# oven.net
KiCad netlist of a schematic drawn in EAGLE
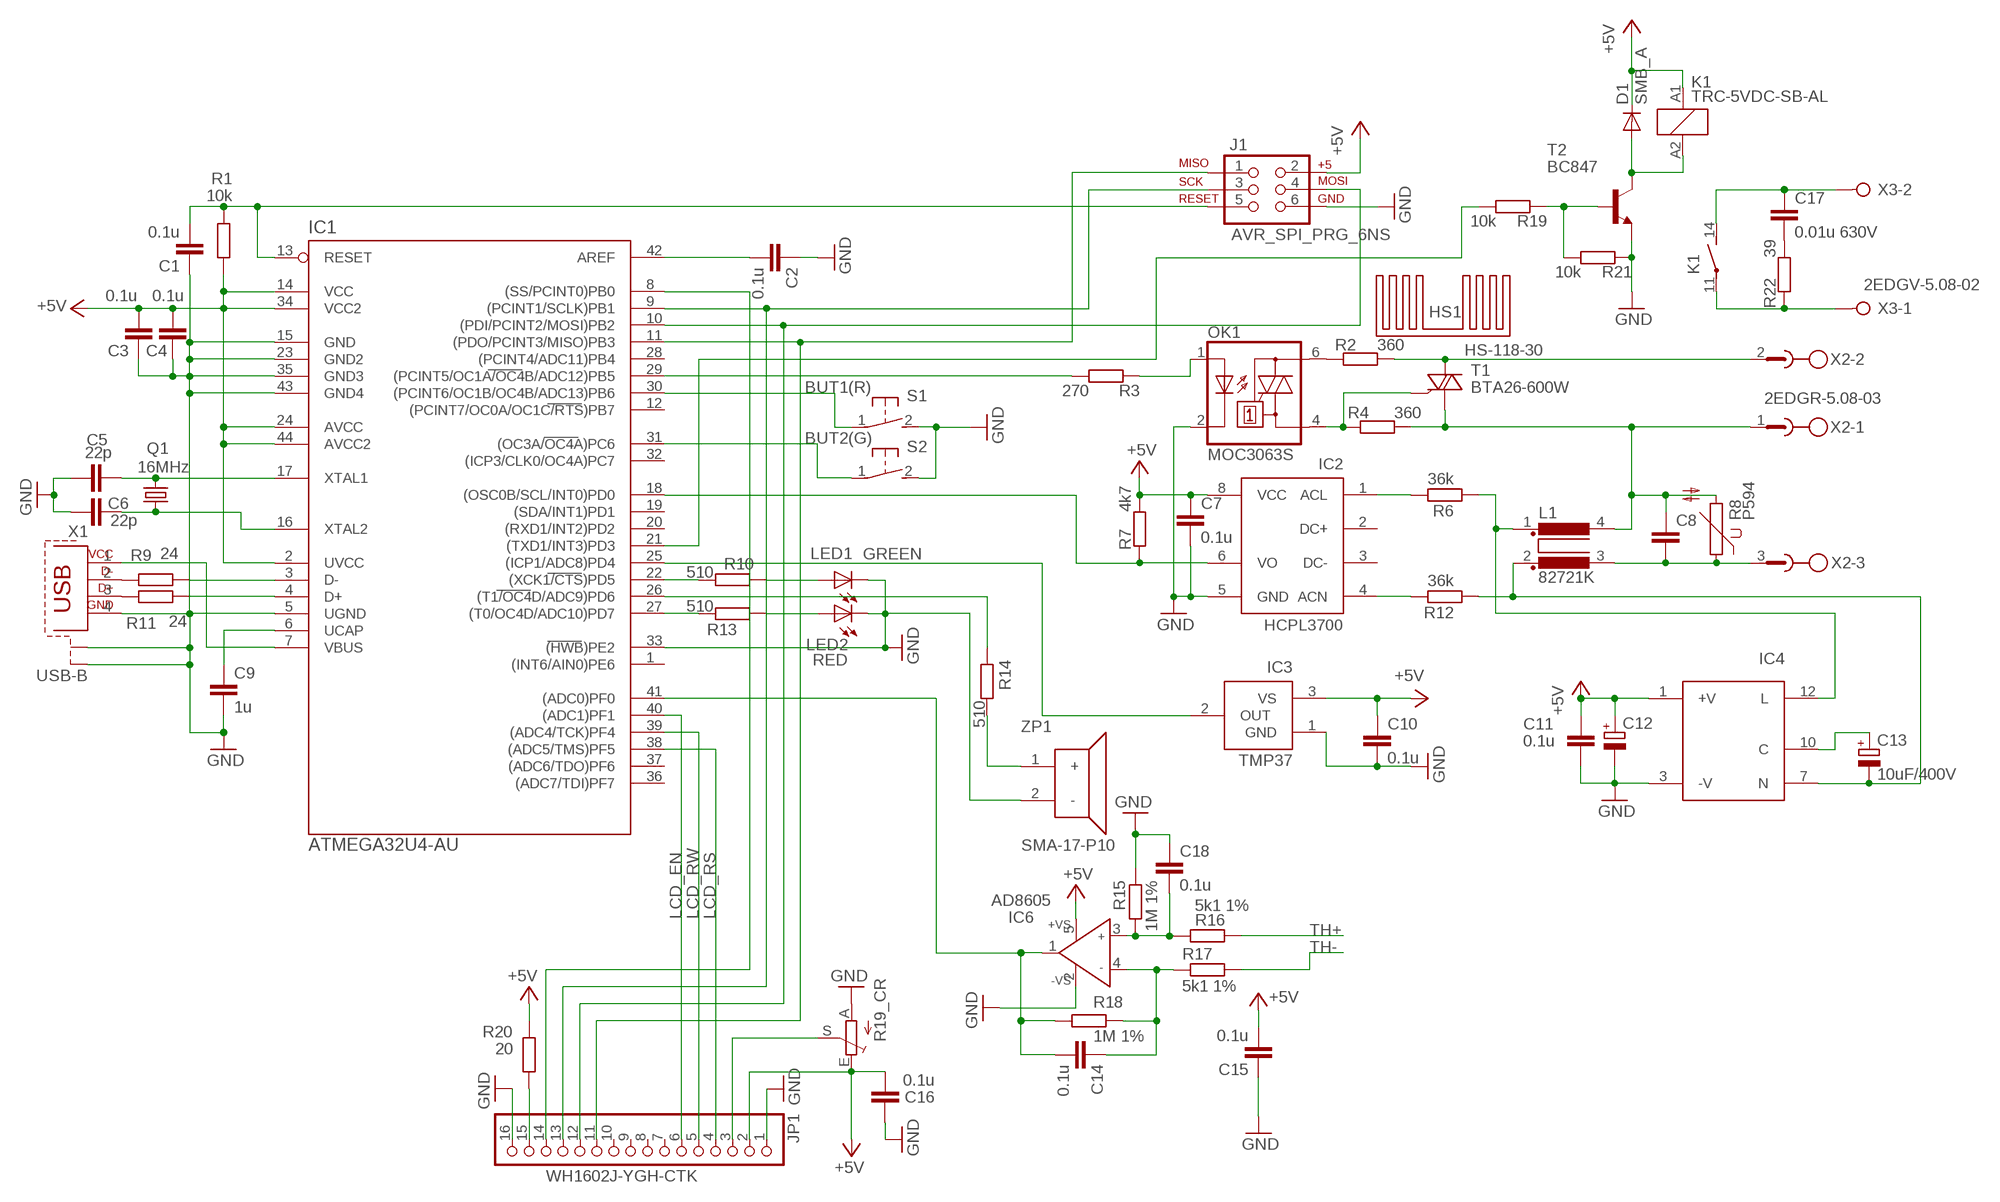
[diagram p0: schematic, sheet 1]

(export (version "E")
  (design (tool "Eeschema 10.0.6"))
  (components
    (comp (ref "C1")
      (value "0.1u")
      (footprint "eagle-import:C0805R")
      (libsource (lib "eagle-import") (part "C-EUC0805R"))
    )
    (comp (ref "C2")
      (value "0.1u")
      (footprint "eagle-import:C0805R")
      (libsource (lib "eagle-import") (part "C-EUC0805R"))
    )
    (comp (ref "C3")
      (value "0.1u")
      (footprint "eagle-import:C0805R")
      (libsource (lib "eagle-import") (part "C-EUC0805R"))
    )
    (comp (ref "C4")
      (value "0.1u")
      (footprint "eagle-import:C0805R")
      (libsource (lib "eagle-import") (part "C-EUC0805R"))
    )
    (comp (ref "C5")
      (value "22p")
      (footprint "eagle-import:C0805R")
      (libsource (lib "eagle-import") (part "C-EUC0805R"))
    )
    (comp (ref "C6")
      (value "22p")
      (footprint "eagle-import:C0805R")
      (libsource (lib "eagle-import") (part "C-EUC0805R"))
    )
    (comp (ref "C7")
      (value "0.1u")
      (footprint "eagle-import:C0805R")
      (libsource (lib "eagle-import") (part "C-EUC0805R"))
    )
    (comp (ref "C8")
      (value "C-EU102-054X133")
      (footprint "eagle-import:C102-054X133")
      (libsource (lib "eagle-import") (part "C-EU102-054X133"))
    )
    (comp (ref "C9")
      (value "1u")
      (footprint "eagle-import:C0805R")
      (libsource (lib "eagle-import") (part "C-EUC0805R"))
    )
    (comp (ref "C10")
      (value "0.1u")
      (footprint "eagle-import:C0805R")
      (libsource (lib "eagle-import") (part "C-EUC0805R"))
    )
    (comp (ref "C11")
      (value "0.1u")
      (footprint "eagle-import:C0805R")
      (libsource (lib "eagle-import") (part "C-EUC0805R"))
    )
    (comp (ref "C12")
      (value "CPOL-EUE3.5-8")
      (footprint "eagle-import:E3,5-8")
      (libsource (lib "eagle-import") (part "CPOL-EUE3.5-8"))
    )
    (comp (ref "C13")
      (value "10uF/400V")
      (footprint "eagle-import:E5-10,5")
      (libsource (lib "eagle-import") (part "CPOL-EUE5-10.5"))
    )
    (comp (ref "C14")
      (value "0.1u")
      (footprint "eagle-import:C0805R")
      (libsource (lib "eagle-import") (part "C-EUC0805R"))
    )
    (comp (ref "C15")
      (value "0.1u")
      (footprint "eagle-import:C0805R")
      (libsource (lib "eagle-import") (part "C-EUC0805R"))
    )
    (comp (ref "C16")
      (value "0.1u")
      (footprint "eagle-import:C0805R")
      (libsource (lib "eagle-import") (part "C-EUC0805R"))
    )
    (comp (ref "C17")
      (value "0.01u 630V")
      (footprint "eagle-import:C102-043X133")
      (libsource (lib "eagle-import") (part "C-EU102-043X133"))
    )
    (comp (ref "C18")
      (value "0.1u")
      (footprint "eagle-import:C0805R")
      (libsource (lib "eagle-import") (part "C-EUC0805R"))
    )
    (comp (ref "D1")
      (value "SMB_A")
      (footprint "eagle-import:DO-214AC")
      (libsource (lib "eagle-import") (part "DIODE-DO-214AC"))
    )
    (comp (ref "HS1")
      (value "HS-118-30")
      (footprint "eagle-import:HS-118")
      (libsource (lib "eagle-import") (part "HS-118"))
    )
    (comp (ref "IC1")
      (value "ATMEGA32U4-AU")
      (footprint "eagle-import:TQFP44")
      (libsource (lib "eagle-import") (part "ATMEGA32U4-AU"))
    )
    (comp (ref "IC2")
      (value "HCPL3700")
      (footprint "eagle-import:DIL08")
      (libsource (lib "eagle-import") (part "HCPL3700"))
    )
    (comp (ref "IC3")
      (value "TMP37")
      (footprint "eagle-import:TO92")
      (libsource (lib "eagle-import") (part "TMP36"))
    )
    (comp (ref "IC4")
      (value "PPM2.5-S12-05ELF")
      (footprint "eagle-import:SIP12")
      (libsource (lib "eagle-import") (part "PPM2.5-S12-05ELF"))
    )
    (comp (ref "IC6")
      (value "AD8605")
      (footprint "eagle-import:SOT23-5")
      (libsource (lib "eagle-import") (part "AD8605"))
    )
    (comp (ref "J1")
      (value "AVR_SPI_PRG_6NS")
      (footprint "eagle-import:2X3-NS")
      (libsource (lib "eagle-import") (part "AVR_SPI_PRG_6NS"))
    )
    (comp (ref "JP1")
      (value "WH1602J-YGH-CTK")
      (footprint "eagle-import:1X16")
      (libsource (lib "eagle-import") (part "PINHD-1X16"))
    )
    (comp (ref "K1")
      (value "TRC-5VDC-SB-AL")
      (footprint "eagle-import:TRC")
      (libsource (lib "eagle-import") (part "TRCA"))
    )
    (comp (ref "L1")
      (value "82721K")
      (footprint "eagle-import:82721K")
      (libsource (lib "eagle-import") (part "82721K"))
    )
    (comp (ref "LED1")
      (value "GREEN")
      (footprint "eagle-import:LED3MM")
      (libsource (lib "eagle-import") (part "LED3MM"))
    )
    (comp (ref "LED2")
      (value "RED")
      (footprint "eagle-import:LED3MM")
      (libsource (lib "eagle-import") (part "LED3MM"))
    )
    (comp (ref "OK1")
      (value "MOC3063S")
      (footprint "eagle-import:DIL6-SMD")
      (fields (field (name "MF") "FAIRCHILD SEMICONDUCTOR") (field (name "MPN") "MOC3043SM"))
      (libsource (lib "eagle-import") (part "MOC30S43"))
    )
    (comp (ref "Q1")
      (value "16MHz")
      (footprint "eagle-import:HC49_S")
      (libsource (lib "eagle-import") (part "CRYSTALHC49S"))
    )
    (comp (ref "R1")
      (value "10k")
      (footprint "eagle-import:R0805R")
      (libsource (lib "eagle-import") (part "R-EU_R0805R"))
    )
    (comp (ref "R2")
      (value "360")
      (footprint "eagle-import:R2512")
      (libsource (lib "eagle-import") (part "R-EU_R2512"))
    )
    (comp (ref "R3")
      (value "270")
      (footprint "eagle-import:R0805R")
      (libsource (lib "eagle-import") (part "R-EU_R0805R"))
    )
    (comp (ref "R4")
      (value "360")
      (footprint "eagle-import:R2512")
      (libsource (lib "eagle-import") (part "R-EU_R2512"))
    )
    (comp (ref "R6")
      (value "36k")
      (footprint "eagle-import:R1206R")
      (libsource (lib "eagle-import") (part "R-EU_R1206R"))
    )
    (comp (ref "R7")
      (value "4k7")
      (footprint "eagle-import:R0805R")
      (libsource (lib "eagle-import") (part "R-EU_R0805R"))
    )
    (comp (ref "R8")
      (value "P594")
      (footprint "eagle-import:P594")
      (libsource (lib "eagle-import") (part "P594"))
    )
    (comp (ref "R9")
      (value "24")
      (footprint "eagle-import:R0805R")
      (libsource (lib "eagle-import") (part "R-EU_R0805R"))
    )
    (comp (ref "R10")
      (value "510")
      (footprint "eagle-import:R0805R")
      (libsource (lib "eagle-import") (part "R-EU_R0805R"))
    )
    (comp (ref "R11")
      (value "24")
      (footprint "eagle-import:R0805R")
      (libsource (lib "eagle-import") (part "R-EU_R0805R"))
    )
    (comp (ref "R12")
      (value "36k")
      (footprint "eagle-import:R1206R")
      (libsource (lib "eagle-import") (part "R-EU_R1206R"))
    )
    (comp (ref "R13")
      (value "510")
      (footprint "eagle-import:R0805R")
      (libsource (lib "eagle-import") (part "R-EU_R0805R"))
    )
    (comp (ref "R14")
      (value "510")
      (footprint "eagle-import:R0805R")
      (libsource (lib "eagle-import") (part "R-EU_R0805R"))
    )
    (comp (ref "R15")
      (value "1M 1%")
      (footprint "eagle-import:R0805R")
      (libsource (lib "eagle-import") (part "R-EU_R0805R"))
    )
    (comp (ref "R16")
      (value "5k1 1%")
      (footprint "eagle-import:R0805R")
      (libsource (lib "eagle-import") (part "R-EU_R0805R"))
    )
    (comp (ref "R17")
      (value "5k1 1%")
      (footprint "eagle-import:R0805R")
      (libsource (lib "eagle-import") (part "R-EU_R0805R"))
    )
    (comp (ref "R18")
      (value "1M 1%")
      (footprint "eagle-import:R0805R")
      (libsource (lib "eagle-import") (part "R-EU_R0805R"))
    )
    (comp (ref "R19")
      (value "10k")
      (footprint "eagle-import:R0805R")
      (libsource (lib "eagle-import") (part "R-EU_R0805R"))
    )
    (comp (ref "R19_CR")
      (value "TRIM_EU-CA6V")
      (footprint "eagle-import:CA6V")
      (libsource (lib "eagle-import") (part "TRIM_EU-CA6V"))
    )
    (comp (ref "R20")
      (value "20")
      (footprint "eagle-import:R0805R")
      (libsource (lib "eagle-import") (part "R-EU_R0805R"))
    )
    (comp (ref "R21")
      (value "10k")
      (footprint "eagle-import:R0805R")
      (libsource (lib "eagle-import") (part "R-EU_R0805R"))
    )
    (comp (ref "R22")
      (value "39")
      (footprint "eagle-import:0207_5V")
      (libsource (lib "eagle-import") (part "R-EU_0207/5V"))
    )
    (comp (ref "S1")
      (value "31-XX")
      (footprint "eagle-import:B3F-31XX")
      (fields (field (name "MPN") "B3F-3100"))
      (libsource (lib "eagle-import") (part "31-XX"))
    )
    (comp (ref "S2")
      (value "31-XX")
      (footprint "eagle-import:B3F-31XX")
      (fields (field (name "MPN") "B3F-3100"))
      (libsource (lib "eagle-import") (part "31-XX"))
    )
    (comp (ref "T1")
      (value "BTA26-600W")
      (footprint "eagle-import:TOP3S-1")
      (libsource (lib "eagle-import") (part "BTA26-V"))
    )
    (comp (ref "T2")
      (value "BC847")
      (footprint "eagle-import:SOT23")
      (libsource (lib "eagle-import") (part "BC847"))
    )
    (comp (ref "X1")
      (value "USB-B")
      (footprint "eagle-import:PN61729-S")
      (libsource (lib "eagle-import") (part "USB-B"))
    )
    (comp (ref "X2")
      (value "2EDGR-5.08-03")
      (footprint "eagle-import:W232-3")
      (libsource (lib "eagle-import") (part "W232-3"))
    )
    (comp (ref "X3")
      (value "2EDGV-5.08-02")
      (footprint "eagle-import:W237-132")
      (libsource (lib "eagle-import") (part "W237-02P"))
    )
    (comp (ref "ZP1")
      (value "SMA-17-P10")
      (footprint "eagle-import:SMA-17")
      (libsource (lib "eagle-import") (part "SMA-17-P10"))
    )
  )
  (nets
    (net (code "1") (name "+5V") (class "Default")
      (node (ref "C10") (pin "1") (pinfunction "1_1") (pintype "passive"))
      (node (ref "C11") (pin "1") (pinfunction "1_1") (pintype "passive"))
      (node (ref "C12") (pin "+") (pinfunction "+_+") (pintype "passive"))
      (node (ref "C15") (pin "2") (pinfunction "2_2") (pintype "passive"))
      (node (ref "C16") (pin "2") (pinfunction "2_2") (pintype "passive"))
      (node (ref "C3") (pin "2") (pinfunction "2_2") (pintype "passive"))
      (node (ref "C4") (pin "2") (pinfunction "2_2") (pintype "passive"))
      (node (ref "C7") (pin "1") (pinfunction "1_1") (pintype "passive"))
      (node (ref "D1") (pin "C") (pinfunction "C_C") (pintype "passive"))
      (node (ref "IC1") (pin "14") (pinfunction "VCC_14") (pintype "bidirectional"))
      (node (ref "IC1") (pin "2") (pinfunction "UVCC_2") (pintype "bidirectional"))
      (node (ref "IC1") (pin "24") (pinfunction "AVCC_24") (pintype "bidirectional"))
      (node (ref "IC1") (pin "34") (pinfunction "VCC2_34") (pintype "bidirectional"))
      (node (ref "IC1") (pin "44") (pinfunction "AVCC2_44") (pintype "bidirectional"))
      (node (ref "IC2") (pin "8") (pinfunction "VCC_8") (pintype "power_in"))
      (node (ref "IC3") (pin "3") (pinfunction "VS_3") (pintype "power_in"))
      (node (ref "IC4") (pin "1") (pinfunction "+V_1") (pintype "bidirectional"))
      (node (ref "IC6") (pin "5") (pinfunction "+VS_5") (pintype "input"))
      (node (ref "J1") (pin "2") (pinfunction "2_2") (pintype "passive"))
      (node (ref "JP1") (pin "2") (pinfunction "2_2") (pintype "passive"))
      (node (ref "K1") (pin "A1") (pinfunction "1_A1") (pintype "passive"))
      (node (ref "R1") (pin "1") (pinfunction "1_1") (pintype "passive"))
      (node (ref "R19_CR") (pin "E") (pinfunction "E_E") (pintype "passive"))
      (node (ref "R20") (pin "1") (pinfunction "1_1") (pintype "passive"))
      (node (ref "R7") (pin "2") (pinfunction "2_2") (pintype "passive"))
    )
    (net (code "2") (name "/BUT1(R)") (class "Default")
      (node (ref "IC1") (pin "30") (pinfunction "(PCINT6/OC1B/OC4B/ADC13)PB6_30") (pintype "bidirectional"))
      (node (ref "S1") (pin "1") (pinfunction "P_1") (pintype "passive"))
    )
    (net (code "3") (name "/BUT2(G)") (class "Default")
      (node (ref "IC1") (pin "31") (pinfunction "(OC3A/OC4A)PC6_31") (pintype "bidirectional"))
      (node (ref "S2") (pin "1") (pinfunction "P_1") (pintype "passive"))
    )
    (net (code "4") (name "/LCD_EN") (class "Default")
      (node (ref "IC1") (pin "40") (pinfunction "(ADC1)PF1_40") (pintype "bidirectional"))
      (node (ref "JP1") (pin "6") (pinfunction "6_6") (pintype "passive"))
    )
    (net (code "5") (name "/LCD_RS") (class "Default")
      (node (ref "IC1") (pin "38") (pinfunction "(ADC5/TMS)PF5_38") (pintype "bidirectional"))
      (node (ref "JP1") (pin "4") (pinfunction "4_4") (pintype "passive"))
    )
    (net (code "6") (name "/LCD_RW") (class "Default")
      (node (ref "IC1") (pin "39") (pinfunction "(ADC4/TCK)PF4_39") (pintype "bidirectional"))
      (node (ref "JP1") (pin "5") (pinfunction "5_5") (pintype "passive"))
    )
    (net (code "7") (name "/TH+") (class "Default")
      (node (ref "R16") (pin "2") (pinfunction "2_2") (pintype "passive"))
    )
    (net (code "8") (name "/TH-") (class "Default")
      (node (ref "R17") (pin "2") (pinfunction "2_2") (pintype "passive"))
    )
    (net (code "9") (name "GND") (class "Default")
      (node (ref "C1") (pin "1") (pinfunction "1_1") (pintype "passive"))
      (node (ref "C10") (pin "2") (pinfunction "2_2") (pintype "passive"))
      (node (ref "C11") (pin "2") (pinfunction "2_2") (pintype "passive"))
      (node (ref "C12") (pin "-") (pinfunction "-_-") (pintype "passive"))
      (node (ref "C15") (pin "1") (pinfunction "1_1") (pintype "passive"))
      (node (ref "C16") (pin "1") (pinfunction "1_1") (pintype "passive"))
      (node (ref "C18") (pin "1") (pinfunction "1_1") (pintype "passive"))
      (node (ref "C2") (pin "1") (pinfunction "1_1") (pintype "passive"))
      (node (ref "C3") (pin "1") (pinfunction "1_1") (pintype "passive"))
      (node (ref "C4") (pin "1") (pinfunction "1_1") (pintype "passive"))
      (node (ref "C5") (pin "1") (pinfunction "1_1") (pintype "passive"))
      (node (ref "C6") (pin "1") (pinfunction "1_1") (pintype "passive"))
      (node (ref "C7") (pin "2") (pinfunction "2_2") (pintype "passive"))
      (node (ref "C9") (pin "2") (pinfunction "2_2") (pintype "passive"))
      (node (ref "IC1") (pin "15") (pinfunction "GND_15") (pintype "bidirectional"))
      (node (ref "IC1") (pin "23") (pinfunction "GND2_23") (pintype "bidirectional"))
      (node (ref "IC1") (pin "33") (pinfunction "(HWB)PE2_33") (pintype "bidirectional"))
      (node (ref "IC1") (pin "35") (pinfunction "GND3_35") (pintype "bidirectional"))
      (node (ref "IC1") (pin "43") (pinfunction "GND4_43") (pintype "bidirectional"))
      (node (ref "IC1") (pin "5") (pinfunction "UGND_5") (pintype "bidirectional"))
      (node (ref "IC2") (pin "5") (pinfunction "GND_5") (pintype "power_in"))
      (node (ref "IC3") (pin "1") (pinfunction "GND_1") (pintype "power_in"))
      (node (ref "IC4") (pin "3") (pinfunction "-V_3") (pintype "bidirectional"))
      (node (ref "IC6") (pin "2") (pinfunction "-VS_2") (pintype "input"))
      (node (ref "J1") (pin "6") (pinfunction "6_6") (pintype "passive"))
      (node (ref "JP1") (pin "1") (pinfunction "1_1") (pintype "passive"))
      (node (ref "JP1") (pin "16") (pinfunction "16_16") (pintype "passive"))
      (node (ref "LED1") (pin "K") (pinfunction "C_K") (pintype "passive"))
      (node (ref "LED2") (pin "K") (pinfunction "C_K") (pintype "passive"))
      (node (ref "OK1") (pin "2") (pinfunction "C_2") (pintype "passive"))
      (node (ref "R15") (pin "2") (pinfunction "2_2") (pintype "passive"))
      (node (ref "R19_CR") (pin "A") (pinfunction "A_A") (pintype "passive"))
      (node (ref "R21") (pin "1") (pinfunction "1_1") (pintype "passive"))
      (node (ref "S1") (pin "2") (pinfunction "S_2") (pintype "passive"))
      (node (ref "S2") (pin "2") (pinfunction "S_2") (pintype "passive"))
      (node (ref "T2") (pin "2") (pinfunction "E_2") (pintype "passive"))
      (node (ref "X1") (pin "4") (pinfunction "4_4") (pintype "passive"))
      (node (ref "X1") (pin "S1") (pinfunction "S1_S1") (pintype "passive"))
      (node (ref "X1") (pin "S2") (pinfunction "S2_S2") (pintype "passive"))
      (node (ref "ZP1") (pin "2") (pinfunction "-_2") (pintype "bidirectional"))
    )
    (net (code "10") (name "Net-(C17-Pad2)") (class "Default")
      (node (ref "C17") (pin "2") (pinfunction "2_2") (pintype "passive"))
      (node (ref "R22") (pin "2") (pinfunction "2_2") (pintype "passive"))
    )
    (net (code "11") (name "Net-(IC1-(ADC0)PF0)") (class "Default")
      (node (ref "C14") (pin "2") (pinfunction "2_2") (pintype "passive"))
      (node (ref "IC1") (pin "41") (pinfunction "(ADC0)PF0_41") (pintype "bidirectional"))
      (node (ref "IC6") (pin "1") (pinfunction "OUT_1") (pintype "output"))
      (node (ref "R18") (pin "1") (pinfunction "1_1") (pintype "passive"))
    )
    (net (code "12") (name "Net-(IC1-(ICP1{slash}ADC8)PD4)") (class "Default")
      (node (ref "IC1") (pin "25") (pinfunction "(ICP1/ADC8)PD4_25") (pintype "bidirectional"))
      (node (ref "IC3") (pin "2") (pinfunction "OUT_2") (pintype "output"))
    )
    (net (code "13") (name "Net-(IC1-(OSC0B{slash}SCL{slash}INT0)PD0)") (class "Default")
      (node (ref "IC1") (pin "18") (pinfunction "(OSC0B/SCL/INT0)PD0_18") (pintype "bidirectional"))
      (node (ref "IC2") (pin "6") (pinfunction "VO_6") (pintype "output"))
      (node (ref "R7") (pin "1") (pinfunction "1_1") (pintype "passive"))
    )
    (net (code "14") (name "Net-(IC1-(PCINT1{slash}SCLK)PB1)") (class "Default")
      (node (ref "IC1") (pin "9") (pinfunction "(PCINT1/SCLK)PB1_9") (pintype "bidirectional"))
      (node (ref "J1") (pin "3") (pinfunction "3_3") (pintype "passive"))
      (node (ref "JP1") (pin "13") (pinfunction "13_13") (pintype "passive"))
    )
    (net (code "15") (name "Net-(IC1-(PCINT5{slash}OC1A{slash}OC4B{slash}ADC12)PB5)") (class "Default")
      (node (ref "IC1") (pin "29") (pinfunction "(PCINT5/OC1A/OC4B/ADC12)PB5_29") (pintype "bidirectional"))
      (node (ref "R3") (pin "2") (pinfunction "2_2") (pintype "passive"))
    )
    (net (code "16") (name "Net-(IC1-(PDI{slash}PCINT2{slash}MOSI)PB2)") (class "Default")
      (node (ref "IC1") (pin "10") (pinfunction "(PDI/PCINT2/MOSI)PB2_10") (pintype "bidirectional"))
      (node (ref "J1") (pin "4") (pinfunction "4_4") (pintype "passive"))
      (node (ref "JP1") (pin "12") (pinfunction "12_12") (pintype "passive"))
    )
    (net (code "17") (name "Net-(IC1-(PDO{slash}PCINT3{slash}MISO)PB3)") (class "Default")
      (node (ref "IC1") (pin "11") (pinfunction "(PDO/PCINT3/MISO)PB3_11") (pintype "bidirectional"))
      (node (ref "J1") (pin "1") (pinfunction "1_1") (pintype "passive"))
      (node (ref "JP1") (pin "11") (pinfunction "11_11") (pintype "passive"))
    )
    (net (code "18") (name "Net-(IC1-(SS{slash}PCINT0)PB0)") (class "Default")
      (node (ref "IC1") (pin "8") (pinfunction "(SS/PCINT0)PB0_8") (pintype "bidirectional"))
      (node (ref "JP1") (pin "14") (pinfunction "14_14") (pintype "passive"))
    )
    (net (code "19") (name "Net-(IC1-(T0{slash}OC4D{slash}ADC10)PD7)") (class "Default")
      (node (ref "IC1") (pin "27") (pinfunction "(T0/OC4D/ADC10)PD7_27") (pintype "bidirectional"))
      (node (ref "R13") (pin "2") (pinfunction "2_2") (pintype "passive"))
    )
    (net (code "20") (name "Net-(IC1-(T1{slash}OC4D{slash}ADC9)PD6)") (class "Default")
      (node (ref "IC1") (pin "26") (pinfunction "(T1/OC4D/ADC9)PD6_26") (pintype "bidirectional"))
      (node (ref "R14") (pin "1") (pinfunction "1_1") (pintype "passive"))
    )
    (net (code "21") (name "Net-(IC1-(TXD1{slash}INT3)PD3)") (class "Default")
      (node (ref "IC1") (pin "21") (pinfunction "(TXD1/INT3)PD3_21") (pintype "bidirectional"))
      (node (ref "R19") (pin "2") (pinfunction "2_2") (pintype "passive"))
    )
    (net (code "22") (name "Net-(IC1-(XCK1{slash}CTS)PD5)") (class "Default")
      (node (ref "IC1") (pin "22") (pinfunction "(XCK1/CTS)PD5_22") (pintype "bidirectional"))
      (node (ref "R10") (pin "2") (pinfunction "2_2") (pintype "passive"))
    )
    (net (code "23") (name "Net-(IC1-AREF)") (class "Default")
      (node (ref "C2") (pin "2") (pinfunction "2_2") (pintype "passive"))
      (node (ref "IC1") (pin "42") (pinfunction "AREF_42") (pintype "bidirectional"))
    )
    (net (code "24") (name "Net-(IC1-D+)") (class "Default")
      (node (ref "IC1") (pin "4") (pinfunction "D+_4") (pintype "bidirectional"))
      (node (ref "R11") (pin "2") (pinfunction "2_2") (pintype "passive"))
    )
    (net (code "25") (name "Net-(IC1-D-)") (class "Default")
      (node (ref "IC1") (pin "3") (pinfunction "D-_3") (pintype "bidirectional"))
      (node (ref "R9") (pin "2") (pinfunction "2_2") (pintype "passive"))
    )
    (net (code "26") (name "Net-(IC1-RESET)") (class "Default")
      (node (ref "C1") (pin "2") (pinfunction "2_2") (pintype "passive"))
      (node (ref "IC1") (pin "13") (pinfunction "RESET_13") (pintype "bidirectional"))
      (node (ref "J1") (pin "5") (pinfunction "5_5") (pintype "passive"))
      (node (ref "R1") (pin "2") (pinfunction "2_2") (pintype "passive"))
    )
    (net (code "27") (name "Net-(IC1-UCAP)") (class "Default")
      (node (ref "C9") (pin "1") (pinfunction "1_1") (pintype "passive"))
      (node (ref "IC1") (pin "6") (pinfunction "UCAP_6") (pintype "bidirectional"))
    )
    (net (code "28") (name "Net-(IC1-VBUS)") (class "Default")
      (node (ref "IC1") (pin "7") (pinfunction "VBUS_7") (pintype "bidirectional"))
      (node (ref "X1") (pin "1") (pinfunction "1_1") (pintype "passive"))
    )
    (net (code "29") (name "Net-(IC1-XTAL1)") (class "Default")
      (node (ref "C5") (pin "2") (pinfunction "2_2") (pintype "passive"))
      (node (ref "IC1") (pin "17") (pinfunction "XTAL1_17") (pintype "bidirectional"))
      (node (ref "Q1") (pin "2") (pinfunction "2_2") (pintype "passive"))
    )
    (net (code "30") (name "Net-(IC1-XTAL2)") (class "Default")
      (node (ref "C6") (pin "2") (pinfunction "2_2") (pintype "passive"))
      (node (ref "IC1") (pin "16") (pinfunction "XTAL2_16") (pintype "bidirectional"))
      (node (ref "Q1") (pin "1") (pinfunction "1_1") (pintype "passive"))
    )
    (net (code "31") (name "Net-(IC2-ACL)") (class "Default")
      (node (ref "IC2") (pin "1") (pinfunction "ACL_1") (pintype "input"))
      (node (ref "R6") (pin "2") (pinfunction "2_2") (pintype "passive"))
    )
    (net (code "32") (name "Net-(IC2-ACN)") (class "Default")
      (node (ref "IC2") (pin "4") (pinfunction "ACN_4") (pintype "input"))
      (node (ref "R12") (pin "2") (pinfunction "2_2") (pintype "passive"))
    )
    (net (code "33") (name "Net-(IC4-C)") (class "Default")
      (node (ref "C13") (pin "+") (pinfunction "+_+") (pintype "passive"))
      (node (ref "IC4") (pin "10") (pinfunction "C_10") (pintype "bidirectional"))
    )
    (net (code "34") (name "Net-(IC4-L)") (class "Default")
      (node (ref "IC4") (pin "12") (pinfunction "L_12") (pintype "bidirectional"))
      (node (ref "L1") (pin "1") (pinfunction "1_1") (pintype "passive"))
      (node (ref "R6") (pin "1") (pinfunction "1_1") (pintype "passive"))
    )
    (net (code "35") (name "Net-(IC4-N)") (class "Default")
      (node (ref "C13") (pin "-") (pinfunction "-_-") (pintype "passive"))
      (node (ref "IC4") (pin "7") (pinfunction "N_7") (pintype "bidirectional"))
      (node (ref "L1") (pin "2") (pinfunction "3_2") (pintype "passive"))
      (node (ref "R12") (pin "1") (pinfunction "1_1") (pintype "passive"))
    )
    (net (code "36") (name "Net-(IC6-IN+)") (class "Default")
      (node (ref "C18") (pin "2") (pinfunction "2_2") (pintype "passive"))
      (node (ref "IC6") (pin "3") (pinfunction "IN+_3") (pintype "input"))
      (node (ref "R15") (pin "1") (pinfunction "1_1") (pintype "passive"))
      (node (ref "R16") (pin "1") (pinfunction "1_1") (pintype "passive"))
    )
    (net (code "37") (name "Net-(IC6-IN-)") (class "Default")
      (node (ref "C14") (pin "1") (pinfunction "1_1") (pintype "passive"))
      (node (ref "IC6") (pin "4") (pinfunction "IN-_4") (pintype "input"))
      (node (ref "R17") (pin "1") (pinfunction "1_1") (pintype "passive"))
      (node (ref "R18") (pin "2") (pinfunction "2_2") (pintype "passive"))
    )
    (net (code "38") (name "Net-(JP1-Pad3)") (class "Default")
      (node (ref "JP1") (pin "3") (pinfunction "3_3") (pintype "passive"))
      (node (ref "R19_CR") (pin "S") (pinfunction "S_S") (pintype "passive"))
    )
    (net (code "39") (name "Net-(JP1-Pad15)") (class "Default")
      (node (ref "JP1") (pin "15") (pinfunction "15_15") (pintype "passive"))
      (node (ref "R20") (pin "2") (pinfunction "2_2") (pintype "passive"))
    )
    (net (code "40") (name "Net-(K1A-2)") (class "Default")
      (node (ref "D1") (pin "A") (pinfunction "A_A") (pintype "passive"))
      (node (ref "K1") (pin "A2") (pinfunction "2_A2") (pintype "passive"))
      (node (ref "T2") (pin "3") (pinfunction "C_3") (pintype "passive"))
    )
    (net (code "41") (name "Net-(K1B-P)") (class "Default")
      (node (ref "K1") (pin "11") (pinfunction "P_11") (pintype "passive"))
      (node (ref "R22") (pin "1") (pinfunction "1_1") (pintype "passive"))
      (node (ref "X3") (pin "1") (pinfunction "KL_1") (pintype "passive"))
    )
    (net (code "42") (name "Net-(K1B-S)") (class "Default")
      (node (ref "C17") (pin "1") (pinfunction "1_1") (pintype "passive"))
      (node (ref "K1") (pin "14") (pinfunction "S_14") (pintype "passive"))
      (node (ref "X3") (pin "2") (pinfunction "KL_2") (pintype "passive"))
    )
    (net (code "43") (name "Net-(L1-2)") (class "Default")
      (node (ref "C8") (pin "1") (pinfunction "1_1") (pintype "passive"))
      (node (ref "L1") (pin "4") (pinfunction "2_4") (pintype "passive"))
      (node (ref "R4") (pin "2") (pinfunction "2_2") (pintype "passive"))
      (node (ref "R8") (pin "2") (pinfunction "2_2") (pintype "passive"))
      (node (ref "T1") (pin "A1") (pinfunction "A1_A1") (pintype "passive"))
      (node (ref "X2") (pin "1") (pinfunction "SK_1") (pintype "passive"))
    )
    (net (code "44") (name "Net-(L1-4)") (class "Default")
      (node (ref "C8") (pin "2") (pinfunction "2_2") (pintype "passive"))
      (node (ref "L1") (pin "3") (pinfunction "4_3") (pintype "passive"))
      (node (ref "R8") (pin "1") (pinfunction "1_1") (pintype "passive"))
      (node (ref "X2") (pin "3") (pinfunction "SK_3") (pintype "passive"))
    )
    (net (code "45") (name "Net-(LED1-PadA)") (class "Default")
      (node (ref "LED1") (pin "A") (pinfunction "A_A") (pintype "passive"))
      (node (ref "R10") (pin "1") (pinfunction "1_1") (pintype "passive"))
    )
    (net (code "46") (name "Net-(LED2-PadA)") (class "Default")
      (node (ref "LED2") (pin "A") (pinfunction "A_A") (pintype "passive"))
      (node (ref "R13") (pin "1") (pinfunction "1_1") (pintype "passive"))
    )
    (net (code "47") (name "Net-(OK1-A)") (class "Default")
      (node (ref "OK1") (pin "1") (pinfunction "A_1") (pintype "passive"))
      (node (ref "R3") (pin "1") (pinfunction "1_1") (pintype "passive"))
    )
    (net (code "48") (name "Net-(OK1-A1)") (class "Default")
      (node (ref "OK1") (pin "4") (pinfunction "A1_4") (pintype "passive"))
      (node (ref "R4") (pin "1") (pinfunction "1_1") (pintype "passive"))
      (node (ref "T1") (pin "G") (pinfunction "G_G") (pintype "passive"))
    )
    (net (code "49") (name "Net-(OK1-A2)") (class "Default")
      (node (ref "OK1") (pin "6") (pinfunction "A2_6") (pintype "passive"))
      (node (ref "R2") (pin "1") (pinfunction "1_1") (pintype "passive"))
    )
    (net (code "50") (name "Net-(R9-Pad1)") (class "Default")
      (node (ref "R9") (pin "1") (pinfunction "1_1") (pintype "passive"))
      (node (ref "X1") (pin "2") (pinfunction "2_2") (pintype "passive"))
    )
    (net (code "51") (name "Net-(R11-Pad1)") (class "Default")
      (node (ref "R11") (pin "1") (pinfunction "1_1") (pintype "passive"))
      (node (ref "X1") (pin "3") (pinfunction "3_3") (pintype "passive"))
    )
    (net (code "52") (name "Net-(T2-B)") (class "Default")
      (node (ref "R19") (pin "1") (pinfunction "1_1") (pintype "passive"))
      (node (ref "R21") (pin "2") (pinfunction "2_2") (pintype "passive"))
      (node (ref "T2") (pin "1") (pinfunction "B_1") (pintype "passive"))
    )
    (net (code "53") (name "Net-(X2B-SK)") (class "Default")
      (node (ref "R2") (pin "2") (pinfunction "2_2") (pintype "passive"))
      (node (ref "T1") (pin "A2") (pinfunction "A2_A2") (pintype "passive"))
      (node (ref "X2") (pin "2") (pinfunction "SK_2") (pintype "passive"))
    )
    (net (code "54") (name "Net-(ZP1-+)") (class "Default")
      (node (ref "R14") (pin "2") (pinfunction "2_2") (pintype "passive"))
      (node (ref "ZP1") (pin "1") (pinfunction "+_1") (pintype "bidirectional"))
    )
    (net (code "55") (name "unconnected-(IC1-(ADC6{slash}TDO)PF6-Pad37)") (class "Default")
      (node (ref "IC1") (pin "37") (pinfunction "(ADC6/TDO)PF6_37") (pintype "bidirectional"))
    )
    (net (code "56") (name "unconnected-(IC1-(ADC7{slash}TDI)PF7-Pad36)") (class "Default")
      (node (ref "IC1") (pin "36") (pinfunction "(ADC7/TDI)PF7_36") (pintype "bidirectional"))
    )
    (net (code "57") (name "unconnected-(IC1-(ICP3{slash}CLK0{slash}OC4A)PC7-Pad32)") (class "Default")
      (node (ref "IC1") (pin "32") (pinfunction "(ICP3/CLK0/OC4A)PC7_32") (pintype "bidirectional"))
    )
    (net (code "58") (name "unconnected-(IC1-(INT6{slash}AIN0)PE6-Pad1)") (class "Default")
      (node (ref "IC1") (pin "1") (pinfunction "(INT6/AIN0)PE6_1") (pintype "bidirectional"))
    )
    (net (code "59") (name "unconnected-(IC1-(PCINT4{slash}ADC11)PB4-Pad28)") (class "Default")
      (node (ref "IC1") (pin "28") (pinfunction "(PCINT4/ADC11)PB4_28") (pintype "bidirectional"))
    )
    (net (code "60") (name "unconnected-(IC1-(PCINT7{slash}OC0A{slash}OC1C{slash}RTS)PB7-Pad12)") (class "Default")
      (node (ref "IC1") (pin "12") (pinfunction "(PCINT7/OC0A/OC1C/RTS)PB7_12") (pintype "bidirectional"))
    )
    (net (code "61") (name "unconnected-(IC1-(RXD1{slash}INT2)PD2-Pad20)") (class "Default")
      (node (ref "IC1") (pin "20") (pinfunction "(RXD1/INT2)PD2_20") (pintype "bidirectional"))
    )
    (net (code "62") (name "unconnected-(IC1-(SDA{slash}INT1)PD1-Pad19)") (class "Default")
      (node (ref "IC1") (pin "19") (pinfunction "(SDA/INT1)PD1_19") (pintype "bidirectional"))
    )
    (net (code "63") (name "unconnected-(IC2-DC+-Pad2)") (class "Default")
      (node (ref "IC2") (pin "2") (pinfunction "DC+_2") (pintype "input"))
    )
    (net (code "64") (name "unconnected-(IC2-DC--Pad3)") (class "Default")
      (node (ref "IC2") (pin "3") (pinfunction "DC-_3") (pintype "input"))
    )
    (net (code "65") (name "unconnected-(JP1-Pad7)") (class "Default")
      (node (ref "JP1") (pin "7") (pinfunction "7_7") (pintype "passive"))
    )
    (net (code "66") (name "unconnected-(JP1-Pad8)") (class "Default")
      (node (ref "JP1") (pin "8") (pinfunction "8_8") (pintype "passive"))
    )
    (net (code "67") (name "unconnected-(JP1-Pad9)") (class "Default")
      (node (ref "JP1") (pin "9") (pinfunction "9_9") (pintype "passive"))
    )
    (net (code "68") (name "unconnected-(JP1-Pad10)") (class "Default")
      (node (ref "JP1") (pin "10") (pinfunction "10_10") (pintype "passive"))
    )
  )
)
